# HP03S_HIH6130.net
KiCad netlist of a schematic drawn in EAGLE
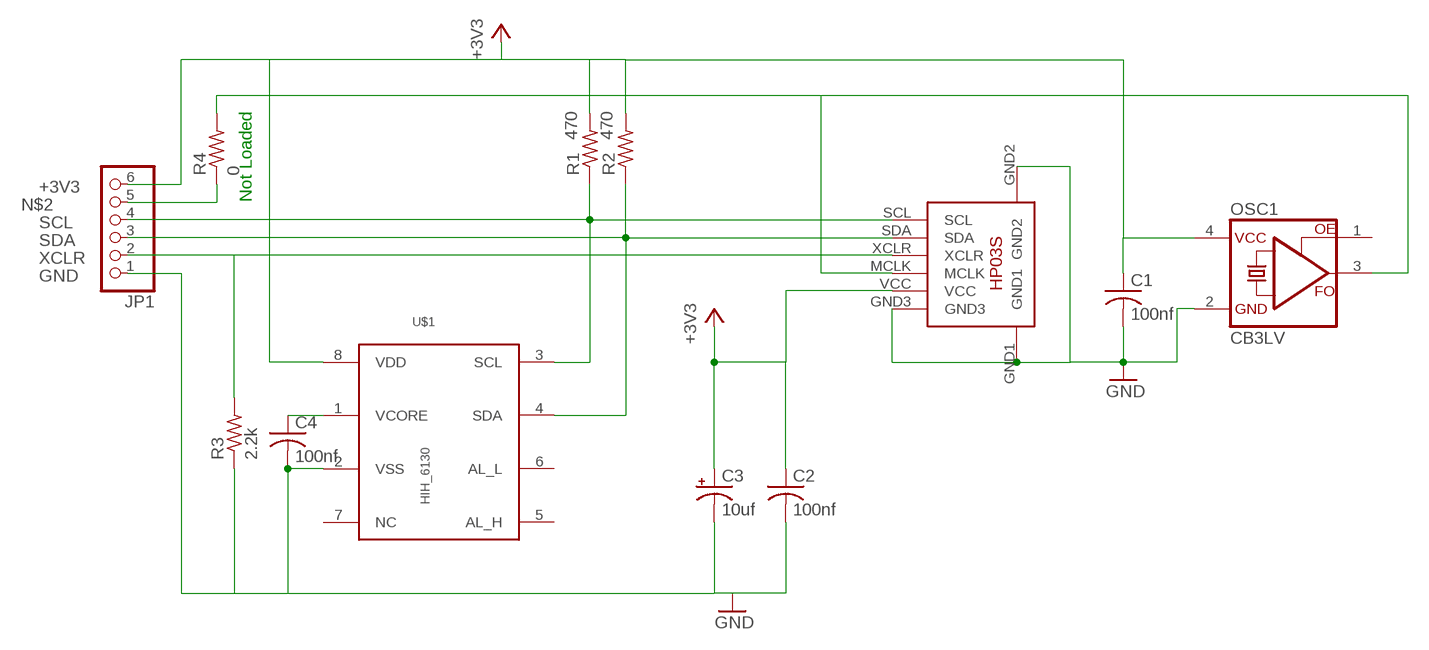
[diagram p0: schematic, sheet 1]

(export (version "E")
  (design (tool "Eeschema 10.0.6"))
  (components
    (comp (ref "C1")
      (value "100nf")
      (footprint "eagle-import:C0805")
      (libsource (lib "eagle-import") (part "C-USC0805"))
    )
    (comp (ref "C2")
      (value "100nf")
      (footprint "eagle-import:C0805K")
      (libsource (lib "eagle-import") (part "C-USC0805K"))
    )
    (comp (ref "C3")
      (value "10uf")
      (footprint "eagle-import:SMC_P")
      (libsource (lib "eagle-import") (part "CPOL-USSMCP"))
    )
    (comp (ref "C4")
      (value "100nf")
      (footprint "eagle-import:C0805K")
      (libsource (lib "eagle-import") (part "C-USC0805K"))
    )
    (comp (ref "JP1")
      (value "PINHD-1X6")
      (footprint "eagle-import:1X06")
      (libsource (lib "eagle-import") (part "PINHD-1X6"))
    )
    (comp (ref "OSC1")
      (value "CB3LV")
      (footprint "eagle-import:SMD7.5X5MM")
      (libsource (lib "eagle-import") (part "CB3LV"))
    )
    (comp (ref "R1")
      (value "470")
      (footprint "eagle-import:R0603")
      (libsource (lib "eagle-import") (part "R-US_R0603"))
    )
    (comp (ref "R2")
      (value "470")
      (footprint "eagle-import:R0603")
      (libsource (lib "eagle-import") (part "R-US_R0603"))
    )
    (comp (ref "R3")
      (value "2.2k")
      (footprint "eagle-import:R0603")
      (libsource (lib "eagle-import") (part "R-US_R0603"))
    )
    (comp (ref "R4")
      (value "0")
      (footprint "eagle-import:R0603")
      (libsource (lib "eagle-import") (part "R-US_R0603"))
    )
    (comp (ref "U$1")
      (value "HIH_6130")
      (footprint "eagle-import:SOIC8")
      (libsource (lib "eagle-import") (part "HIH_6130"))
    )
    (comp (ref "U$2")
      (value "HP03S")
      (footprint "eagle-import:HP03S")
      (libsource (lib "eagle-import") (part "HP03S"))
    )
  )
  (nets
    (net (code "1") (name "+3V3") (class "Default")
      (node (ref "C1") (pin "1") (pinfunction "1_1") (pintype "passive"))
      (node (ref "C2") (pin "1") (pinfunction "1_1") (pintype "passive"))
      (node (ref "C3") (pin "+") (pinfunction "+_+") (pintype "passive"))
      (node (ref "JP1") (pin "6") (pinfunction "6_6") (pintype "passive"))
      (node (ref "OSC1") (pin "4") (pinfunction "VCC_4") (pintype "power_in"))
      (node (ref "R1") (pin "2") (pinfunction "2_2") (pintype "passive"))
      (node (ref "R2") (pin "2") (pinfunction "2_2") (pintype "passive"))
      (node (ref "U$1") (pin "8") (pinfunction "VDD_8") (pintype "bidirectional"))
      (node (ref "U$2") (pin "VCC") (pinfunction "VCC_VCC") (pintype "bidirectional"))
    )
    (net (code "2") (name "/N$2") (class "Default")
      (node (ref "JP1") (pin "5") (pinfunction "5_5") (pintype "passive"))
      (node (ref "R4") (pin "1") (pinfunction "1_1") (pintype "passive"))
    )
    (net (code "3") (name "/SCL") (class "Default")
      (node (ref "JP1") (pin "4") (pinfunction "4_4") (pintype "passive"))
      (node (ref "R1") (pin "1") (pinfunction "1_1") (pintype "passive"))
      (node (ref "U$1") (pin "3") (pinfunction "SCL_3") (pintype "bidirectional"))
      (node (ref "U$2") (pin "SCL") (pinfunction "SCL_SCL") (pintype "bidirectional"))
    )
    (net (code "4") (name "/SDA") (class "Default")
      (node (ref "JP1") (pin "3") (pinfunction "3_3") (pintype "passive"))
      (node (ref "R2") (pin "1") (pinfunction "1_1") (pintype "passive"))
      (node (ref "U$1") (pin "4") (pinfunction "SDA_4") (pintype "bidirectional"))
      (node (ref "U$2") (pin "SDA") (pinfunction "SDA_SDA") (pintype "bidirectional"))
    )
    (net (code "5") (name "/XCLR") (class "Default")
      (node (ref "JP1") (pin "2") (pinfunction "2_2") (pintype "passive"))
      (node (ref "R3") (pin "2") (pinfunction "2_2") (pintype "passive"))
      (node (ref "U$2") (pin "XCLR") (pinfunction "XCLR_XCLR") (pintype "bidirectional"))
    )
    (net (code "6") (name "GND") (class "Default")
      (node (ref "C1") (pin "2") (pinfunction "2_2") (pintype "passive"))
      (node (ref "C2") (pin "2") (pinfunction "2_2") (pintype "passive"))
      (node (ref "C3") (pin "-") (pinfunction "-_-") (pintype "passive"))
      (node (ref "C4") (pin "2") (pinfunction "2_2") (pintype "passive"))
      (node (ref "JP1") (pin "1") (pinfunction "1_1") (pintype "passive"))
      (node (ref "OSC1") (pin "2") (pinfunction "GND_2") (pintype "power_in"))
      (node (ref "R3") (pin "1") (pinfunction "1_1") (pintype "passive"))
      (node (ref "U$1") (pin "2") (pinfunction "VSS_2") (pintype "bidirectional"))
      (node (ref "U$2") (pin "GND1") (pinfunction "GND1_GND1") (pintype "bidirectional"))
      (node (ref "U$2") (pin "GND2") (pinfunction "GND2_GND2") (pintype "bidirectional"))
      (node (ref "U$2") (pin "GND3") (pinfunction "GND3_GND3") (pintype "bidirectional"))
    )
    (net (code "7") (name "Net-(OSC1-FO)") (class "Default")
      (node (ref "OSC1") (pin "3") (pinfunction "FO_3") (pintype "output"))
      (node (ref "R4") (pin "2") (pinfunction "2_2") (pintype "passive"))
      (node (ref "U$2") (pin "MCLK") (pinfunction "MCLK_MCLK") (pintype "bidirectional"))
    )
    (net (code "8") (name "Net-(U$1-VCORE)") (class "Default")
      (node (ref "C4") (pin "1") (pinfunction "1_1") (pintype "passive"))
      (node (ref "U$1") (pin "1") (pinfunction "VCORE_1") (pintype "bidirectional"))
    )
    (net (code "9") (name "unconnected-(OSC1-OE-Pad1)") (class "Default")
      (node (ref "OSC1") (pin "1") (pinfunction "OE_1") (pintype "input"))
    )
    (net (code "10") (name "unconnected-(U$1-AL_H-Pad5)") (class "Default")
      (node (ref "U$1") (pin "5") (pinfunction "AL_H_5") (pintype "bidirectional"))
    )
    (net (code "11") (name "unconnected-(U$1-AL_L-Pad6)") (class "Default")
      (node (ref "U$1") (pin "6") (pinfunction "AL_L_6") (pintype "bidirectional"))
    )
    (net (code "12") (name "unconnected-(U$1-NC-Pad7)") (class "Default")
      (node (ref "U$1") (pin "7") (pinfunction "NC_7") (pintype "bidirectional"))
    )
  )
)
